# nanoCUL_v3_4.net
KiCad netlist of a schematic drawn in EAGLE
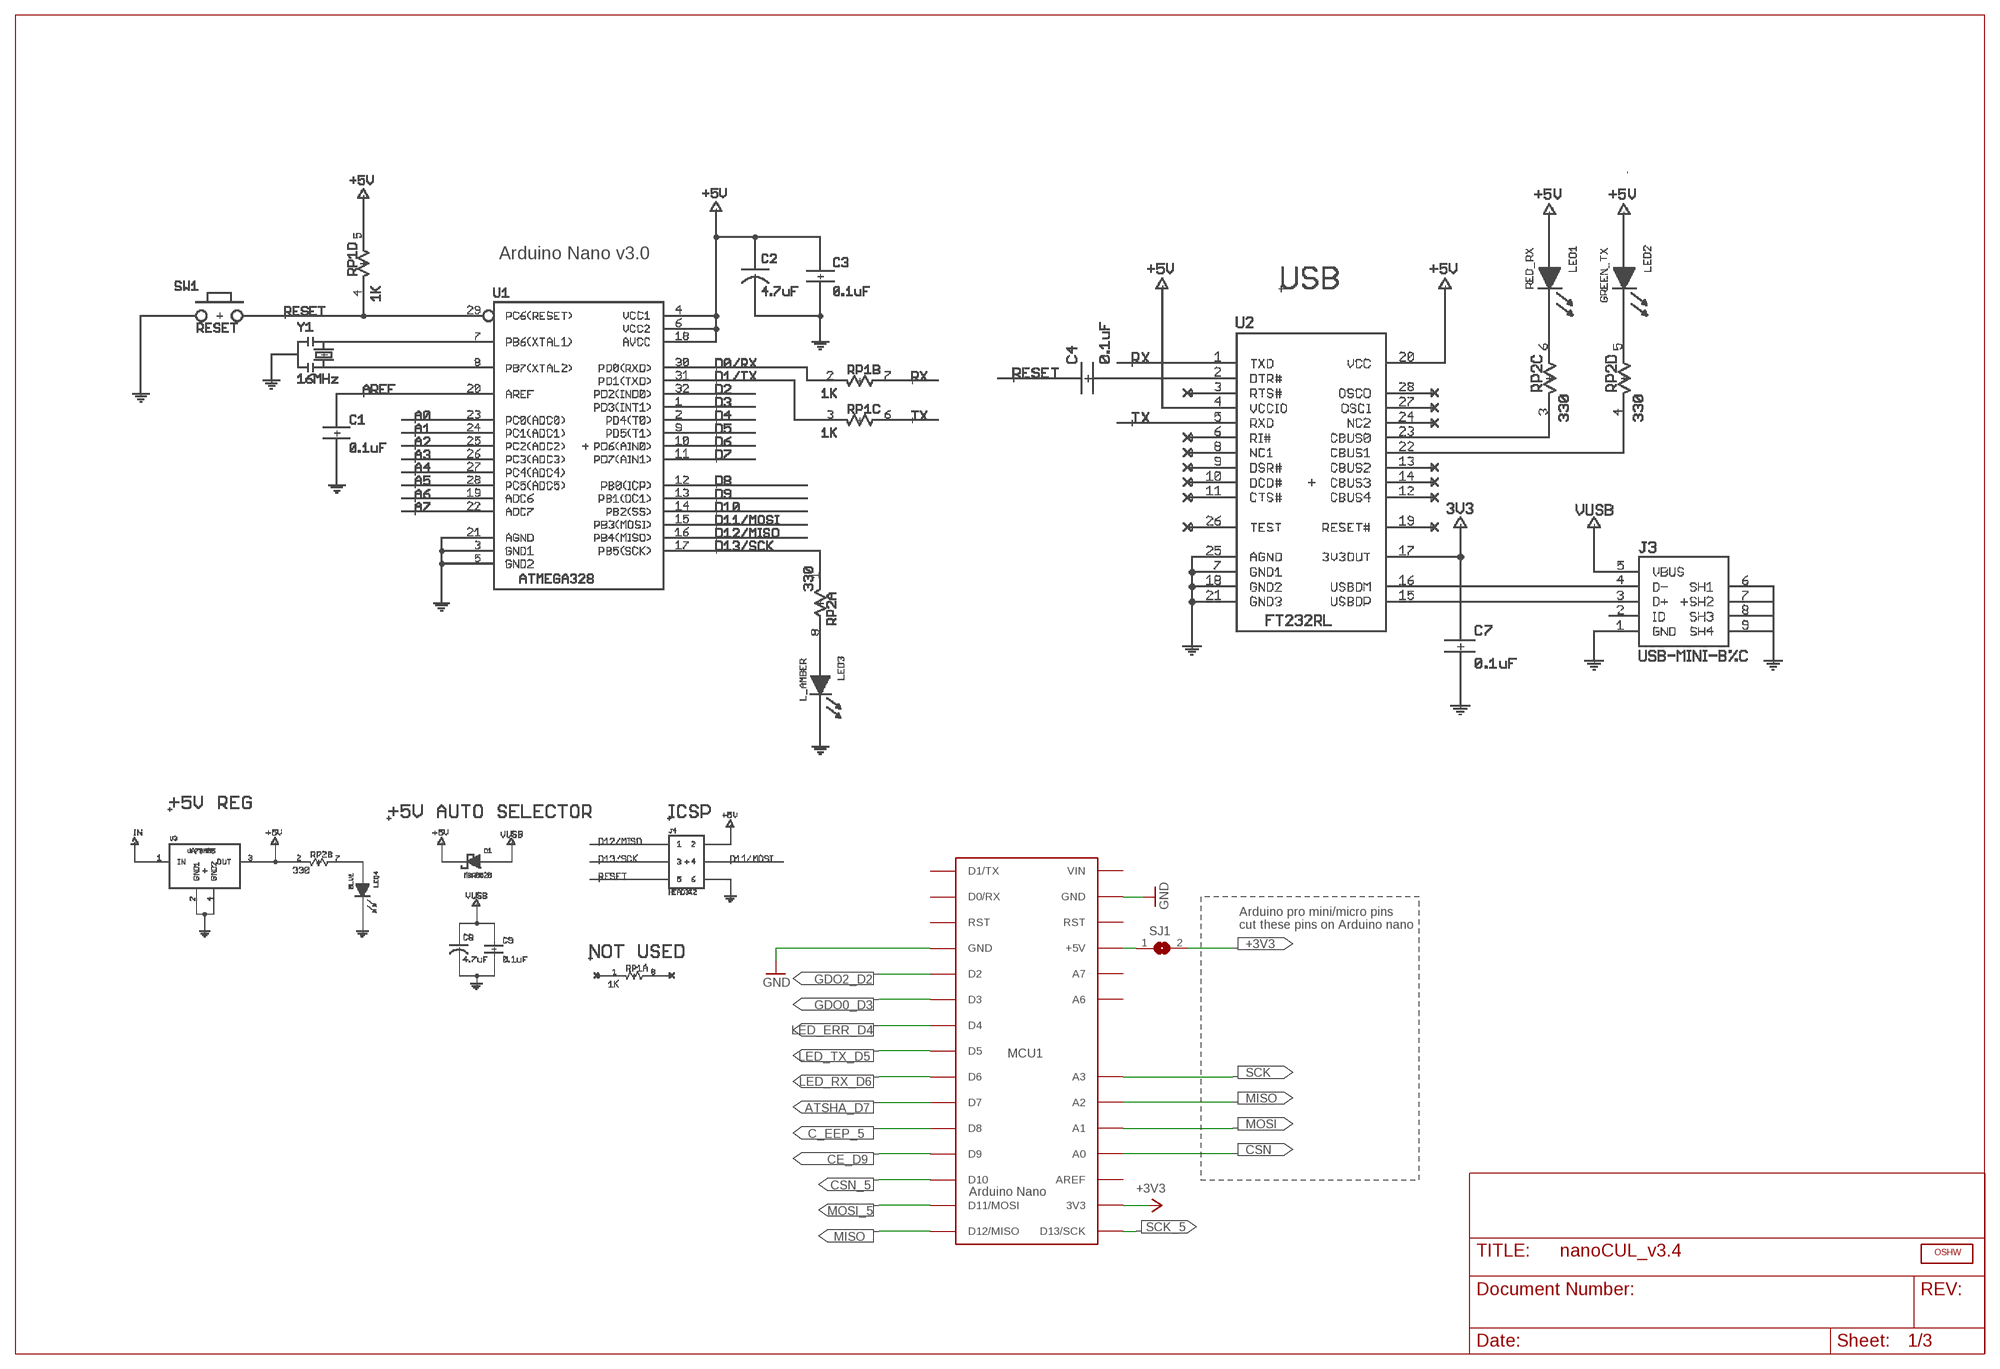
[diagram p0: schematic, sheet 1]
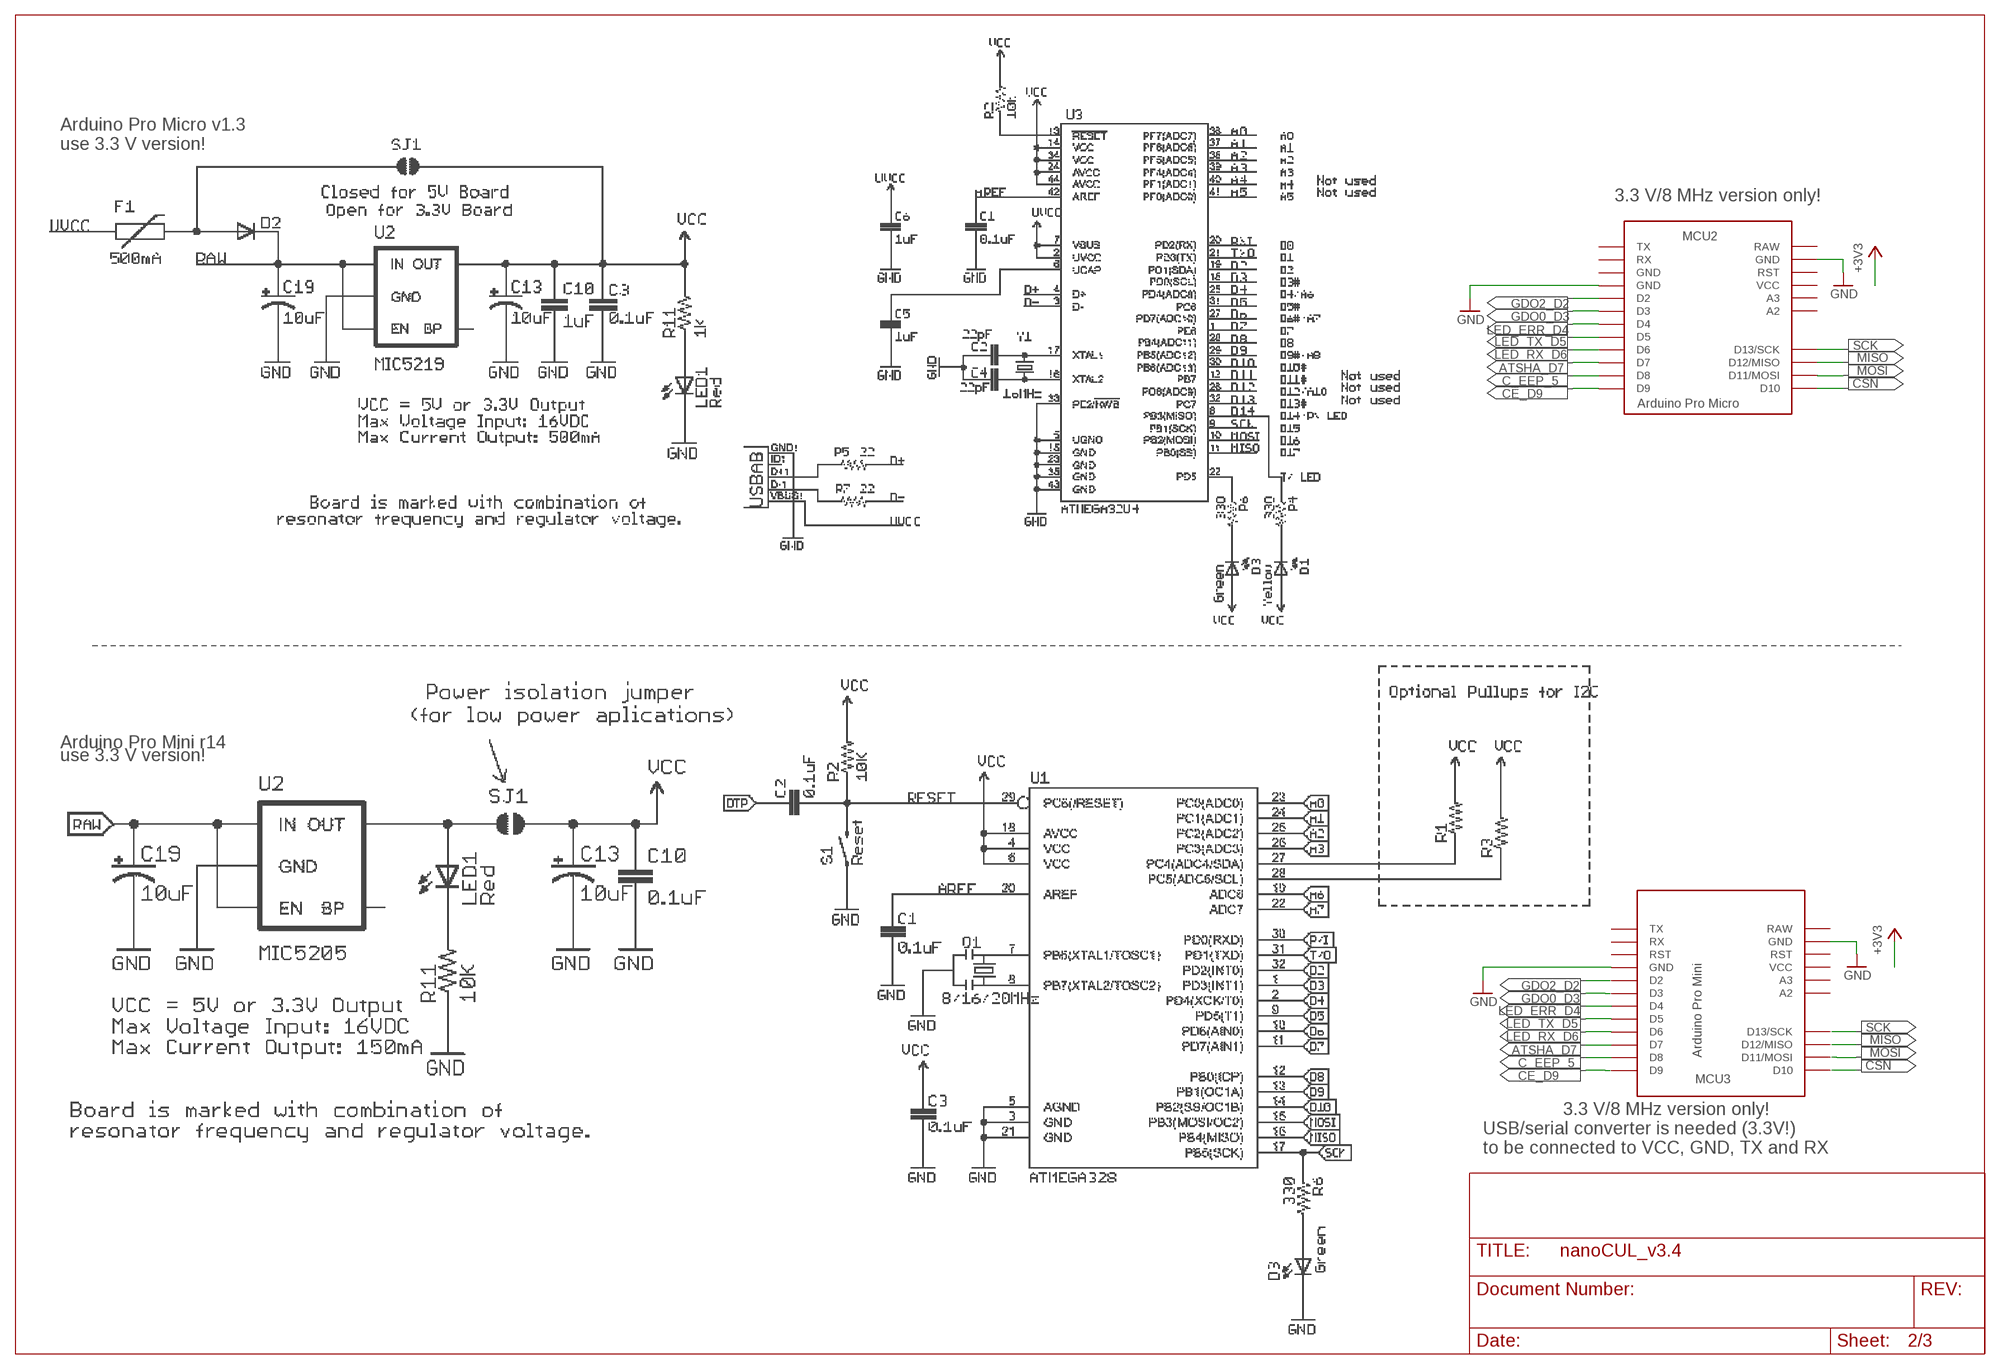
[diagram p1: schematic, sheet 2]
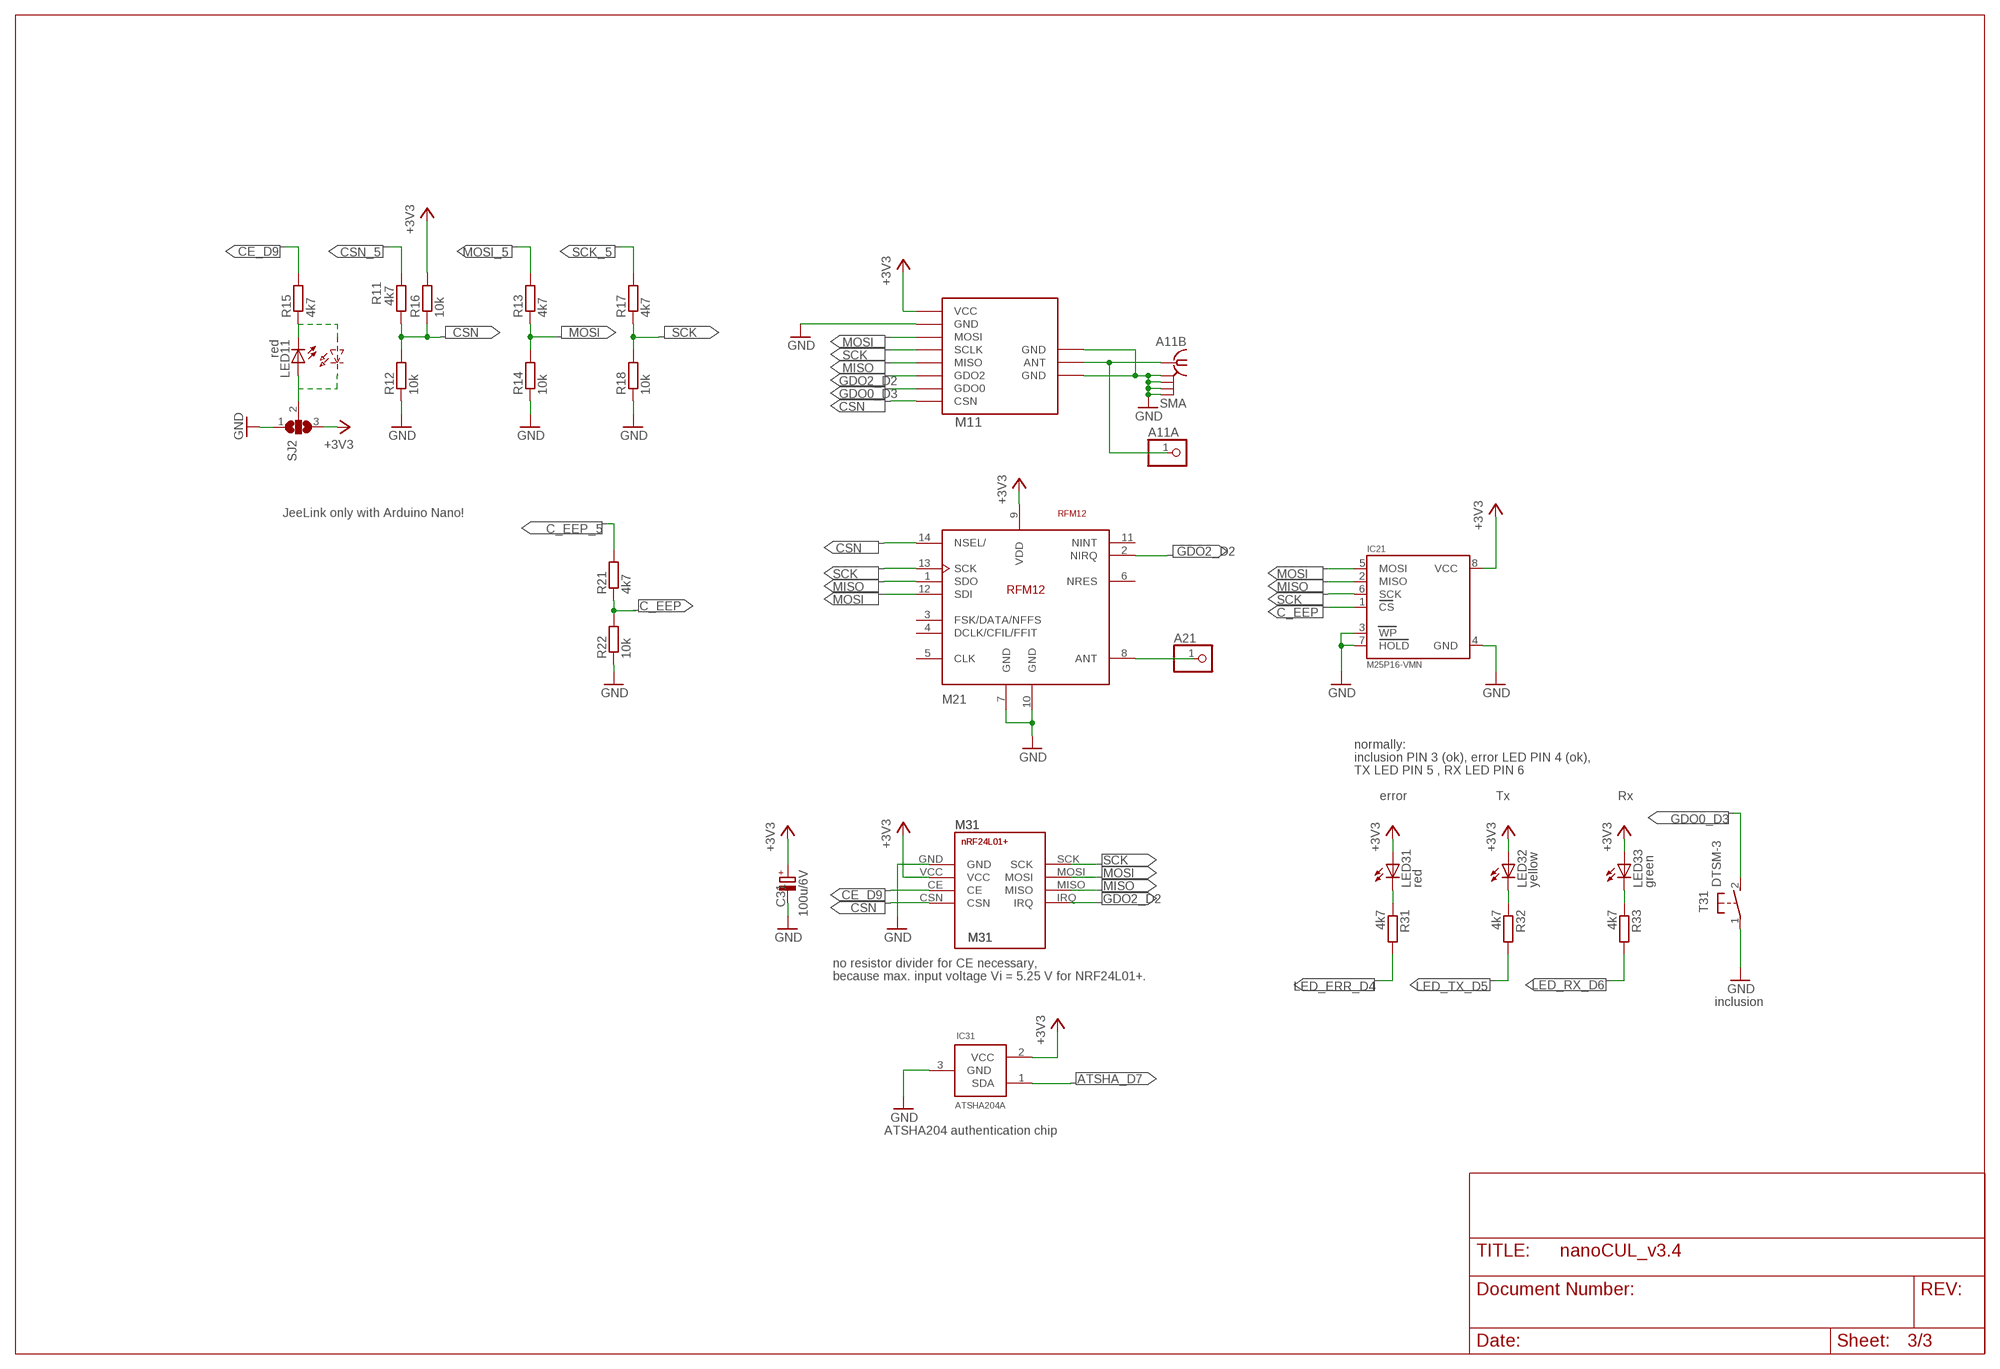
[diagram p2: schematic, sheet 3]

(export (version "E")
  (design (tool "Eeschema 10.0.6"))
  (components
    (comp (ref "MCU2")
      (value "ARDUINO_PRO_MICRO_NO_A0-A1")
      (footprint "eagle-import:ARDUINO_PRO_MICRO_NO_A0-A1")
      (libsource (lib "eagle-import") (part "ARDUINO_PRO_MICRO_NO_A0-A1"))
    )
    (comp (ref "MCU3")
      (value "ARDUINO_PRO_MINI_NO_A0-A1")
      (footprint "eagle-import:ARDUINO_PRO_MINI_NO_A0-A1")
      (libsource (lib "eagle-import") (part "ARDUINO_PRO_MINI_NO_A0-A1"))
    )
    (comp (ref "LOGO1")
      (value "LOGO_OSHWX0070")
      (footprint "eagle-import:OSHW_6X70")
      (libsource (lib "eagle-import") (part "LOGO_OSHWX0070"))
    )
    (comp (ref "MCU1")
      (value "ARDUINO_NANO_NO_A4-A5")
      (footprint "eagle-import:ARDUINO_NANO_NO_A4-A5")
      (libsource (lib "eagle-import") (part "ARDUINO_NANO_NO_A4-A5"))
    )
    (comp (ref "SJ1") (value "SJ") (footprint "eagle-import:SJ") (libsource (lib "eagle-import") (part "SJ")))
    (comp (ref "A11A")
      (value "PINHD-1X1")
      (footprint "eagle-import:1X01")
      (libsource (lib "eagle-import") (part "PINHD-1X1"))
    )
    (comp (ref "A11B")
      (value "SMA")
      (footprint "eagle-import:SMA")
      (libsource (lib "eagle-import") (part "SMA"))
    )
    (comp (ref "A21")
      (value "PINHD-1X1")
      (footprint "eagle-import:1X01")
      (libsource (lib "eagle-import") (part "PINHD-1X1"))
    )
    (comp (ref "C31")
      (value "100u/6V")
      (footprint "eagle-import:CT3528")
      (libsource (lib "eagle-import") (part "CPOL-EUCT3528"))
    )
    (comp (ref "IC21")
      (value "M25P16-VMN")
      (footprint "eagle-import:SOIC8")
      (libsource (lib "eagle-import") (part "EEPROM_SPI_AT25040A"))
    )
    (comp (ref "IC31")
      (value "ATSHA204A")
      (footprint "eagle-import:SOT23")
      (libsource (lib "eagle-import") (part "ATSHA204A"))
    )
    (comp (ref "LED11")
      (value "red")
      (footprint "eagle-import:CHIPLED_1206")
      (libsource (lib "eagle-import") (part "LEDCHIPLED_1206"))
    )
    (comp (ref "LED31")
      (value "red")
      (footprint "eagle-import:CHIPLED_1206")
      (libsource (lib "eagle-import") (part "LEDCHIPLED_1206"))
    )
    (comp (ref "LED32")
      (value "yellow")
      (footprint "eagle-import:CHIPLED_1206")
      (libsource (lib "eagle-import") (part "LEDCHIPLED_1206"))
    )
    (comp (ref "LED33")
      (value "green")
      (footprint "eagle-import:CHIPLED_1206")
      (libsource (lib "eagle-import") (part "LEDCHIPLED_1206"))
    )
    (comp (ref "M11")
      (value "CC1101_MODULE1DIL_BIG")
      (footprint "eagle-import:CC1101_MODULE1_DIL-2")
      (libsource (lib "eagle-import") (part "CC1101_MODULE1DIL_BIG"))
    )
    (comp (ref "M21")
      (value "RFM12")
      (footprint "eagle-import:RFM12_SMALL")
      (libsource (lib "eagle-import") (part "RFM12SMALL"))
    )
    (comp (ref "M31")
      (value "NRF24L01+SMD")
      (footprint "eagle-import:NRF24L01+SMD")
      (libsource (lib "eagle-import") (part "NRF24L01+SMD"))
    )
    (comp (ref "R11")
      (value "4k7")
      (footprint "eagle-import:R0805")
      (libsource (lib "eagle-import") (part "R-EU_R0805"))
    )
    (comp (ref "R12")
      (value "10k")
      (footprint "eagle-import:R0805")
      (libsource (lib "eagle-import") (part "R-EU_R0805"))
    )
    (comp (ref "R13")
      (value "4k7")
      (footprint "eagle-import:R0805")
      (libsource (lib "eagle-import") (part "R-EU_R0805"))
    )
    (comp (ref "R14")
      (value "10k")
      (footprint "eagle-import:R0805")
      (libsource (lib "eagle-import") (part "R-EU_R0805"))
    )
    (comp (ref "R15")
      (value "4k7")
      (footprint "eagle-import:R0805")
      (libsource (lib "eagle-import") (part "R-EU_R0805"))
    )
    (comp (ref "R16")
      (value "10k")
      (footprint "eagle-import:R0805")
      (libsource (lib "eagle-import") (part "R-EU_R0805"))
    )
    (comp (ref "R17")
      (value "4k7")
      (footprint "eagle-import:R0805")
      (libsource (lib "eagle-import") (part "R-EU_R0805"))
    )
    (comp (ref "R18")
      (value "10k")
      (footprint "eagle-import:R0805")
      (libsource (lib "eagle-import") (part "R-EU_R0805"))
    )
    (comp (ref "R21")
      (value "4k7")
      (footprint "eagle-import:R0805")
      (libsource (lib "eagle-import") (part "R-EU_R0805"))
    )
    (comp (ref "R22")
      (value "10k")
      (footprint "eagle-import:R0805")
      (libsource (lib "eagle-import") (part "R-EU_R0805"))
    )
    (comp (ref "R31")
      (value "4k7")
      (footprint "eagle-import:R0805")
      (libsource (lib "eagle-import") (part "R-EU_R0805"))
    )
    (comp (ref "R32")
      (value "4k7")
      (footprint "eagle-import:R0805")
      (libsource (lib "eagle-import") (part "R-EU_R0805"))
    )
    (comp (ref "R33")
      (value "4k7")
      (footprint "eagle-import:R0805")
      (libsource (lib "eagle-import") (part "R-EU_R0805"))
    )
    (comp (ref "SJ2")
      (value "SJ2W")
      (footprint "eagle-import:SJ_2")
      (libsource (lib "eagle-import") (part "SJ2W"))
    )
    (comp (ref "T31")
      (value "DTSM-3")
      (footprint "eagle-import:DTSM-3")
      (libsource (lib "eagle-import") (part "DTSM-3"))
    )
  )
  (nets
    (net (code "1") (name "+3V3") (class "Default")
      (node (ref "C31") (pin "+") (pinfunction "+_+") (pintype "passive"))
      (node (ref "IC21") (pin "8") (pinfunction "VCC_8") (pintype "power_in"))
      (node (ref "IC31") (pin "2") (pinfunction "VCC_2") (pintype "bidirectional"))
      (node (ref "LED31") (pin "A") (pinfunction "A_A") (pintype "passive"))
      (node (ref "LED32") (pin "A") (pinfunction "A_A") (pintype "passive"))
      (node (ref "LED33") (pin "A") (pinfunction "A_A") (pintype "passive"))
      (node (ref "M11") (pin "1") (pinfunction "VCC_1") (pintype "power_in"))
      (node (ref "M21") (pin "9") (pinfunction "VDD_9") (pintype "power_in"))
      (node (ref "M31") (pin "VCC") (pinfunction "VCC_VCC") (pintype "power_in"))
      (node (ref "MCU1") (pin "3V3") (pinfunction "3V3_3V3") (pintype "bidirectional"))
      (node (ref "R16") (pin "2") (pinfunction "2_2") (pintype "passive"))
      (node (ref "SJ1") (pin "2") (pinfunction "2_2") (pintype "passive"))
      (node (ref "SJ2") (pin "3") (pinfunction "3_3") (pintype "passive"))
    )
    (net (code "2") (name "ATSHA_D7") (class "Default")
      (node (ref "IC31") (pin "1") (pinfunction "SDA_1") (pintype "bidirectional"))
      (node (ref "MCU1") (pin "D7") (pinfunction "D7_D7") (pintype "bidirectional"))
      (node (ref "MCU2") (pin "D7") (pinfunction "D7_D7") (pintype "bidirectional"))
      (node (ref "MCU3") (pin "D7") (pinfunction "D7_D7") (pintype "bidirectional"))
    )
    (net (code "3") (name "CE_D9") (class "Default")
      (node (ref "M31") (pin "CE") (pinfunction "CE_CE") (pintype "bidirectional"))
      (node (ref "MCU1") (pin "D9") (pinfunction "D9_D9") (pintype "bidirectional"))
      (node (ref "MCU2") (pin "D9") (pinfunction "D9_D9") (pintype "bidirectional"))
      (node (ref "MCU3") (pin "D9") (pinfunction "D9_D9") (pintype "bidirectional"))
      (node (ref "R15") (pin "2") (pinfunction "2_2") (pintype "passive"))
    )
    (net (code "4") (name "CSN") (class "Default")
      (node (ref "M11") (pin "8") (pinfunction "CSN_8") (pintype "bidirectional"))
      (node (ref "M21") (pin "14") (pinfunction "NSEL/_14") (pintype "input"))
      (node (ref "M31") (pin "CSN") (pinfunction "CSN_CSN") (pintype "bidirectional"))
      (node (ref "MCU1") (pin "A0") (pinfunction "A0_A0") (pintype "bidirectional"))
      (node (ref "MCU2") (pin "D10") (pinfunction "D10_D10") (pintype "bidirectional"))
      (node (ref "MCU3") (pin "D10") (pinfunction "D10_D10") (pintype "bidirectional"))
      (node (ref "R11") (pin "1") (pinfunction "1_1") (pintype "passive"))
      (node (ref "R12") (pin "2") (pinfunction "2_2") (pintype "passive"))
      (node (ref "R16") (pin "1") (pinfunction "1_1") (pintype "passive"))
    )
    (net (code "5") (name "CSN_5") (class "Default")
      (node (ref "MCU1") (pin "D10") (pinfunction "D10_D10") (pintype "bidirectional"))
      (node (ref "R11") (pin "2") (pinfunction "2_2") (pintype "passive"))
    )
    (net (code "6") (name "C_EEP") (class "Default")
      (node (ref "IC21") (pin "1") (pinfunction "CS_1") (pintype "bidirectional"))
      (node (ref "R21") (pin "1") (pinfunction "1_1") (pintype "passive"))
      (node (ref "R22") (pin "2") (pinfunction "2_2") (pintype "passive"))
    )
    (net (code "7") (name "C_EEP_5") (class "Default")
      (node (ref "MCU1") (pin "D8") (pinfunction "D8_D8") (pintype "bidirectional"))
      (node (ref "MCU2") (pin "D8") (pinfunction "D8_D8") (pintype "bidirectional"))
      (node (ref "MCU3") (pin "D8") (pinfunction "D8_D8") (pintype "bidirectional"))
      (node (ref "R21") (pin "2") (pinfunction "2_2") (pintype "passive"))
    )
    (net (code "8") (name "GDO0_D3") (class "Default")
      (node (ref "M11") (pin "7") (pinfunction "GDO0_7") (pintype "bidirectional"))
      (node (ref "MCU1") (pin "D3") (pinfunction "D3_D3") (pintype "bidirectional"))
      (node (ref "MCU2") (pin "D3") (pinfunction "D3_D3") (pintype "bidirectional"))
      (node (ref "MCU3") (pin "D3") (pinfunction "D3_D3") (pintype "bidirectional"))
      (node (ref "T31") (pin "2") (pinfunction "2_2") (pintype "passive"))
    )
    (net (code "9") (name "GDO2_D2") (class "Default")
      (node (ref "M11") (pin "6") (pinfunction "GDO2_6") (pintype "bidirectional"))
      (node (ref "M21") (pin "2") (pinfunction "NIRQ_2") (pintype "output"))
      (node (ref "M31") (pin "IRQ") (pinfunction "IRQ_IRQ") (pintype "bidirectional"))
      (node (ref "MCU1") (pin "D2") (pinfunction "D2_D2") (pintype "bidirectional"))
      (node (ref "MCU2") (pin "D2") (pinfunction "D2_D2") (pintype "bidirectional"))
      (node (ref "MCU3") (pin "D2") (pinfunction "D2_D2") (pintype "bidirectional"))
    )
    (net (code "10") (name "GND") (class "Default")
      (node (ref "A11B") (pin "GND@1") (pinfunction "2_GND@1") (pintype "passive"))
      (node (ref "A11B") (pin "GND@2") (pinfunction "3_GND@2") (pintype "passive"))
      (node (ref "A11B") (pin "GND@3") (pinfunction "4_GND@3") (pintype "passive"))
      (node (ref "A11B") (pin "GND@4") (pinfunction "5_GND@4") (pintype "passive"))
      (node (ref "C31") (pin "-") (pinfunction "-_-") (pintype "passive"))
      (node (ref "IC21") (pin "3") (pinfunction "WP_3") (pintype "bidirectional"))
      (node (ref "IC21") (pin "4") (pinfunction "GND_4") (pintype "power_in"))
      (node (ref "IC21") (pin "7") (pinfunction "HOLD_7") (pintype "bidirectional"))
      (node (ref "IC31") (pin "3") (pinfunction "GND_3") (pintype "bidirectional"))
      (node (ref "M11") (pin "11") (pinfunction "GND_11") (pintype "power_in"))
      (node (ref "M11") (pin "2") (pinfunction "GND_2") (pintype "power_in"))
      (node (ref "M11") (pin "9") (pinfunction "GND_9") (pintype "power_in"))
      (node (ref "M21") (pin "10") (pinfunction "GND_10") (pintype "passive"))
      (node (ref "M21") (pin "7") (pinfunction "GND_7") (pintype "passive"))
      (node (ref "M31") (pin "GND") (pinfunction "GND_GND") (pintype "power_in"))
      (node (ref "MCU1") (pin "GND@0") (pinfunction "GND_GND@0") (pintype "bidirectional"))
      (node (ref "MCU1") (pin "GND@1") (pinfunction "GND_GND@1") (pintype "bidirectional"))
      (node (ref "MCU2") (pin "GND@1") (pinfunction "GND_GND@1") (pintype "bidirectional"))
      (node (ref "MCU2") (pin "GND@2") (pinfunction "GND_GND@2") (pintype "bidirectional"))
      (node (ref "MCU3") (pin "GND@0") (pinfunction "GND_GND@0") (pintype "bidirectional"))
      (node (ref "MCU3") (pin "GND@1") (pinfunction "GND_GND@1") (pintype "bidirectional"))
      (node (ref "R12") (pin "1") (pinfunction "1_1") (pintype "passive"))
      (node (ref "R14") (pin "1") (pinfunction "1_1") (pintype "passive"))
      (node (ref "R18") (pin "1") (pinfunction "1_1") (pintype "passive"))
      (node (ref "R22") (pin "1") (pinfunction "1_1") (pintype "passive"))
      (node (ref "SJ2") (pin "1") (pinfunction "1_1") (pintype "passive"))
      (node (ref "T31") (pin "1") (pinfunction "1_1") (pintype "passive"))
    )
    (net (code "11") (name "LED_ERR_D4") (class "Default")
      (node (ref "MCU1") (pin "D4") (pinfunction "D4_D4") (pintype "bidirectional"))
      (node (ref "MCU2") (pin "D4") (pinfunction "D4_D4") (pintype "bidirectional"))
      (node (ref "MCU3") (pin "D4") (pinfunction "D4_D4") (pintype "bidirectional"))
      (node (ref "R31") (pin "2") (pinfunction "2_2") (pintype "passive"))
    )
    (net (code "12") (name "LED_RX_D6") (class "Default")
      (node (ref "MCU1") (pin "D6") (pinfunction "D6_D6") (pintype "bidirectional"))
      (node (ref "MCU2") (pin "D6") (pinfunction "D6_D6") (pintype "bidirectional"))
      (node (ref "MCU3") (pin "D6") (pinfunction "D6_D6") (pintype "bidirectional"))
      (node (ref "R33") (pin "2") (pinfunction "2_2") (pintype "passive"))
    )
    (net (code "13") (name "LED_TX_D5") (class "Default")
      (node (ref "MCU1") (pin "D5") (pinfunction "D5_D5") (pintype "bidirectional"))
      (node (ref "MCU2") (pin "D5") (pinfunction "D5_D5") (pintype "bidirectional"))
      (node (ref "MCU3") (pin "D5") (pinfunction "D5_D5") (pintype "bidirectional"))
      (node (ref "R32") (pin "2") (pinfunction "2_2") (pintype "passive"))
    )
    (net (code "14") (name "MISO") (class "Default")
      (node (ref "IC21") (pin "2") (pinfunction "MISO_2") (pintype "bidirectional"))
      (node (ref "M11") (pin "5") (pinfunction "MISO_5") (pintype "bidirectional"))
      (node (ref "M21") (pin "1") (pinfunction "SDO_1") (pintype "output"))
      (node (ref "M31") (pin "MISO") (pinfunction "MISO_MISO") (pintype "bidirectional"))
      (node (ref "MCU1") (pin "A2") (pinfunction "A2_A2") (pintype "bidirectional"))
      (node (ref "MCU1") (pin "D12") (pinfunction "D12/MISO_D12") (pintype "bidirectional"))
      (node (ref "MCU2") (pin "D12/MISO") (pinfunction "D12/MISO_D12/MISO") (pintype "bidirectional"))
      (node (ref "MCU3") (pin "D12/MISO") (pinfunction "D12/MISO_D12/MISO") (pintype "bidirectional"))
    )
    (net (code "15") (name "MOSI") (class "Default")
      (node (ref "IC21") (pin "5") (pinfunction "MOSI_5") (pintype "bidirectional"))
      (node (ref "M11") (pin "3") (pinfunction "MOSI_3") (pintype "bidirectional"))
      (node (ref "M21") (pin "12") (pinfunction "SDI_12") (pintype "input"))
      (node (ref "M31") (pin "MOSI") (pinfunction "MOSI_MOSI") (pintype "bidirectional"))
      (node (ref "MCU1") (pin "A1") (pinfunction "A1_A1") (pintype "bidirectional"))
      (node (ref "MCU2") (pin "D11/MOSI") (pinfunction "D11/MOSI_D11/MOSI") (pintype "bidirectional"))
      (node (ref "MCU3") (pin "D11/MOSI") (pinfunction "D11/MOSI_D11/MOSI") (pintype "bidirectional"))
      (node (ref "R13") (pin "1") (pinfunction "1_1") (pintype "passive"))
      (node (ref "R14") (pin "2") (pinfunction "2_2") (pintype "passive"))
    )
    (net (code "16") (name "MOSI_5") (class "Default")
      (node (ref "MCU1") (pin "D11") (pinfunction "D11/MOSI_D11") (pintype "bidirectional"))
      (node (ref "R13") (pin "2") (pinfunction "2_2") (pintype "passive"))
    )
    (net (code "17") (name "Net-(LED11-PadA)") (class "Default")
      (node (ref "LED11") (pin "A") (pinfunction "A_A") (pintype "passive"))
      (node (ref "SJ2") (pin "2") (pinfunction "2_2") (pintype "passive"))
    )
    (net (code "18") (name "Net-(LED11-PadC)") (class "Default")
      (node (ref "LED11") (pin "C") (pinfunction "C_C") (pintype "passive"))
      (node (ref "R15") (pin "1") (pinfunction "1_1") (pintype "passive"))
    )
    (net (code "19") (name "Net-(LED31-PadC)") (class "Default")
      (node (ref "LED31") (pin "C") (pinfunction "C_C") (pintype "passive"))
      (node (ref "R31") (pin "1") (pinfunction "1_1") (pintype "passive"))
    )
    (net (code "20") (name "Net-(LED32-PadC)") (class "Default")
      (node (ref "LED32") (pin "C") (pinfunction "C_C") (pintype "passive"))
      (node (ref "R32") (pin "1") (pinfunction "1_1") (pintype "passive"))
    )
    (net (code "21") (name "Net-(LED33-PadC)") (class "Default")
      (node (ref "LED33") (pin "C") (pinfunction "C_C") (pintype "passive"))
      (node (ref "R33") (pin "1") (pinfunction "1_1") (pintype "passive"))
    )
    (net (code "22") (name "Net-(M11-ANT)") (class "Default")
      (node (ref "A11A") (pin "1") (pinfunction "1_1") (pintype "passive"))
      (node (ref "A11B") (pin "1") (pinfunction "1_1") (pintype "passive"))
      (node (ref "M11") (pin "10") (pinfunction "ANT_10") (pintype "output"))
    )
    (net (code "23") (name "Net-(M21-ANT)") (class "Default")
      (node (ref "A21") (pin "1") (pinfunction "1_1") (pintype "passive"))
      (node (ref "M21") (pin "8") (pinfunction "ANT_8") (pintype "bidirectional"))
    )
    (net (code "24") (name "Net-(MCU1-Pad+5V)") (class "Default")
      (node (ref "MCU1") (pin "+5V") (pinfunction "+5V_+5V") (pintype "bidirectional"))
      (node (ref "SJ1") (pin "1") (pinfunction "1_1") (pintype "passive"))
    )
    (net (code "25") (name "SCK") (class "Default")
      (node (ref "IC21") (pin "6") (pinfunction "SCK_6") (pintype "bidirectional"))
      (node (ref "M11") (pin "4") (pinfunction "SCLK_4") (pintype "bidirectional"))
      (node (ref "M21") (pin "13") (pinfunction "SCK_13") (pintype "input"))
      (node (ref "M31") (pin "SCK") (pinfunction "SCK_SCK") (pintype "bidirectional"))
      (node (ref "MCU1") (pin "A3") (pinfunction "A3_A3") (pintype "bidirectional"))
      (node (ref "MCU2") (pin "D13/SCK") (pinfunction "D13/SCK_D13/SCK") (pintype "bidirectional"))
      (node (ref "MCU3") (pin "D13/SCK") (pinfunction "D13/SCK_D13/SCK") (pintype "bidirectional"))
      (node (ref "R17") (pin "1") (pinfunction "1_1") (pintype "passive"))
      (node (ref "R18") (pin "2") (pinfunction "2_2") (pintype "passive"))
    )
    (net (code "26") (name "SCK_5") (class "Default")
      (node (ref "MCU1") (pin "D13") (pinfunction "D13/SCK_D13") (pintype "bidirectional"))
      (node (ref "R17") (pin "2") (pinfunction "2_2") (pintype "passive"))
    )
    (net (code "27") (name "unconnected-(M21-CLK-Pad5)") (class "Default")
      (node (ref "M21") (pin "5") (pinfunction "CLK_5") (pintype "output"))
    )
    (net (code "28") (name "unconnected-(M21-DCLK{slash}CFIL{slash}FFIT-Pad4)") (class "Default")
      (node (ref "M21") (pin "4") (pinfunction "DCLK/CFIL/FFIT_4") (pintype "bidirectional"))
    )
    (net (code "29") (name "unconnected-(M21-FSK{slash}DATA{slash}NFFS-Pad3)") (class "Default")
      (node (ref "M21") (pin "3") (pinfunction "FSK/DATA/NFFS_3") (pintype "bidirectional"))
    )
    (net (code "30") (name "unconnected-(M21-NINT-Pad11)") (class "Default")
      (node (ref "M21") (pin "11") (pinfunction "NINT_11") (pintype "bidirectional"))
    )
    (net (code "31") (name "unconnected-(M21-NRES-Pad6)") (class "Default")
      (node (ref "M21") (pin "6") (pinfunction "NRES_6") (pintype "bidirectional"))
    )
    (net (code "32") (name "unconnected-(MCU1-PadA6)") (class "Default")
      (node (ref "MCU1") (pin "A6") (pinfunction "A6_A6") (pintype "bidirectional"))
    )
    (net (code "33") (name "unconnected-(MCU1-PadA7)") (class "Default")
      (node (ref "MCU1") (pin "A7") (pinfunction "A7_A7") (pintype "bidirectional"))
    )
    (net (code "34") (name "unconnected-(MCU1-PadAREF)") (class "Default")
      (node (ref "MCU1") (pin "AREF") (pinfunction "AREF_AREF") (pintype "bidirectional"))
    )
    (net (code "35") (name "unconnected-(MCU1-PadD0{slash}RX)") (class "Default")
      (node (ref "MCU1") (pin "D0/RX") (pinfunction "D0/RX_D0/RX") (pintype "bidirectional"))
    )
    (net (code "36") (name "unconnected-(MCU1-PadD1{slash}TX)") (class "Default")
      (node (ref "MCU1") (pin "D1/TX") (pinfunction "D1/TX_D1/TX") (pintype "bidirectional"))
    )
    (net (code "37") (name "unconnected-(MCU1-PadVIN)") (class "Default")
      (node (ref "MCU1") (pin "VIN") (pinfunction "VIN_VIN") (pintype "bidirectional"))
    )
    (net (code "38") (name "unconnected-(MCU1-RST-PadRESET@0)") (class "Default")
      (node (ref "MCU1") (pin "RESET@0") (pinfunction "RST_RESET@0") (pintype "bidirectional"))
    )
    (net (code "39") (name "unconnected-(MCU1-RST-PadRESET@1)") (class "Default")
      (node (ref "MCU1") (pin "RESET@1") (pinfunction "RST_RESET@1") (pintype "bidirectional"))
    )
    (net (code "40") (name "unconnected-(MCU2-GND-PadGND@0)") (class "Default")
      (node (ref "MCU2") (pin "GND@0") (pinfunction "GND_GND@0") (pintype "bidirectional"))
    )
    (net (code "41") (name "unconnected-(MCU2-PadA2)") (class "Default")
      (node (ref "MCU2") (pin "A2") (pinfunction "A2_A2") (pintype "bidirectional"))
    )
    (net (code "42") (name "unconnected-(MCU2-PadA3)") (class "Default")
      (node (ref "MCU2") (pin "A3") (pinfunction "A3_A3") (pintype "bidirectional"))
    )
    (net (code "43") (name "unconnected-(MCU2-PadRAW)") (class "Default")
      (node (ref "MCU2") (pin "RAW") (pinfunction "RAW_RAW") (pintype "bidirectional"))
    )
    (net (code "44") (name "unconnected-(MCU2-PadRST)") (class "Default")
      (node (ref "MCU2") (pin "RST") (pinfunction "RST_RST") (pintype "bidirectional"))
    )
    (net (code "45") (name "unconnected-(MCU2-PadRX)") (class "Default")
      (node (ref "MCU2") (pin "RX") (pinfunction "RX_RX") (pintype "bidirectional"))
    )
    (net (code "46") (name "unconnected-(MCU2-PadTX)") (class "Default")
      (node (ref "MCU2") (pin "TX") (pinfunction "TX_TX") (pintype "bidirectional"))
    )
    (net (code "47") (name "unconnected-(MCU2-PadVCC)") (class "Default")
      (node (ref "MCU2") (pin "VCC") (pinfunction "VCC_VCC") (pintype "bidirectional"))
    )
    (net (code "48") (name "unconnected-(MCU3-PadA2)") (class "Default")
      (node (ref "MCU3") (pin "A2") (pinfunction "A2_A2") (pintype "bidirectional"))
    )
    (net (code "49") (name "unconnected-(MCU3-PadA3)") (class "Default")
      (node (ref "MCU3") (pin "A3") (pinfunction "A3_A3") (pintype "bidirectional"))
    )
    (net (code "50") (name "unconnected-(MCU3-PadRAW)") (class "Default")
      (node (ref "MCU3") (pin "RAW") (pinfunction "RAW_RAW") (pintype "bidirectional"))
    )
    (net (code "51") (name "unconnected-(MCU3-RST-PadRST@0)") (class "Default")
      (node (ref "MCU3") (pin "RST@0") (pinfunction "RST_RST@0") (pintype "bidirectional"))
    )
    (net (code "52") (name "unconnected-(MCU3-RST-PadRST@1)") (class "Default")
      (node (ref "MCU3") (pin "RST@1") (pinfunction "RST_RST@1") (pintype "bidirectional"))
    )
    (net (code "53") (name "unconnected-(MCU3-RX-PadRX@0)") (class "Default")
      (node (ref "MCU3") (pin "RX@0") (pinfunction "RX_RX@0") (pintype "bidirectional"))
    )
    (net (code "54") (name "unconnected-(MCU3-TX-PadTX@0)") (class "Default")
      (node (ref "MCU3") (pin "TX@0") (pinfunction "TX_TX@0") (pintype "bidirectional"))
    )
    (net (code "55") (name "unconnected-(MCU3-VCC-PadVCC@0)") (class "Default")
      (node (ref "MCU3") (pin "VCC@0") (pinfunction "VCC_VCC@0") (pintype "bidirectional"))
    )
  )
)
